# FPGA_34.net
KiCad netlist of a schematic drawn in Altium Designer
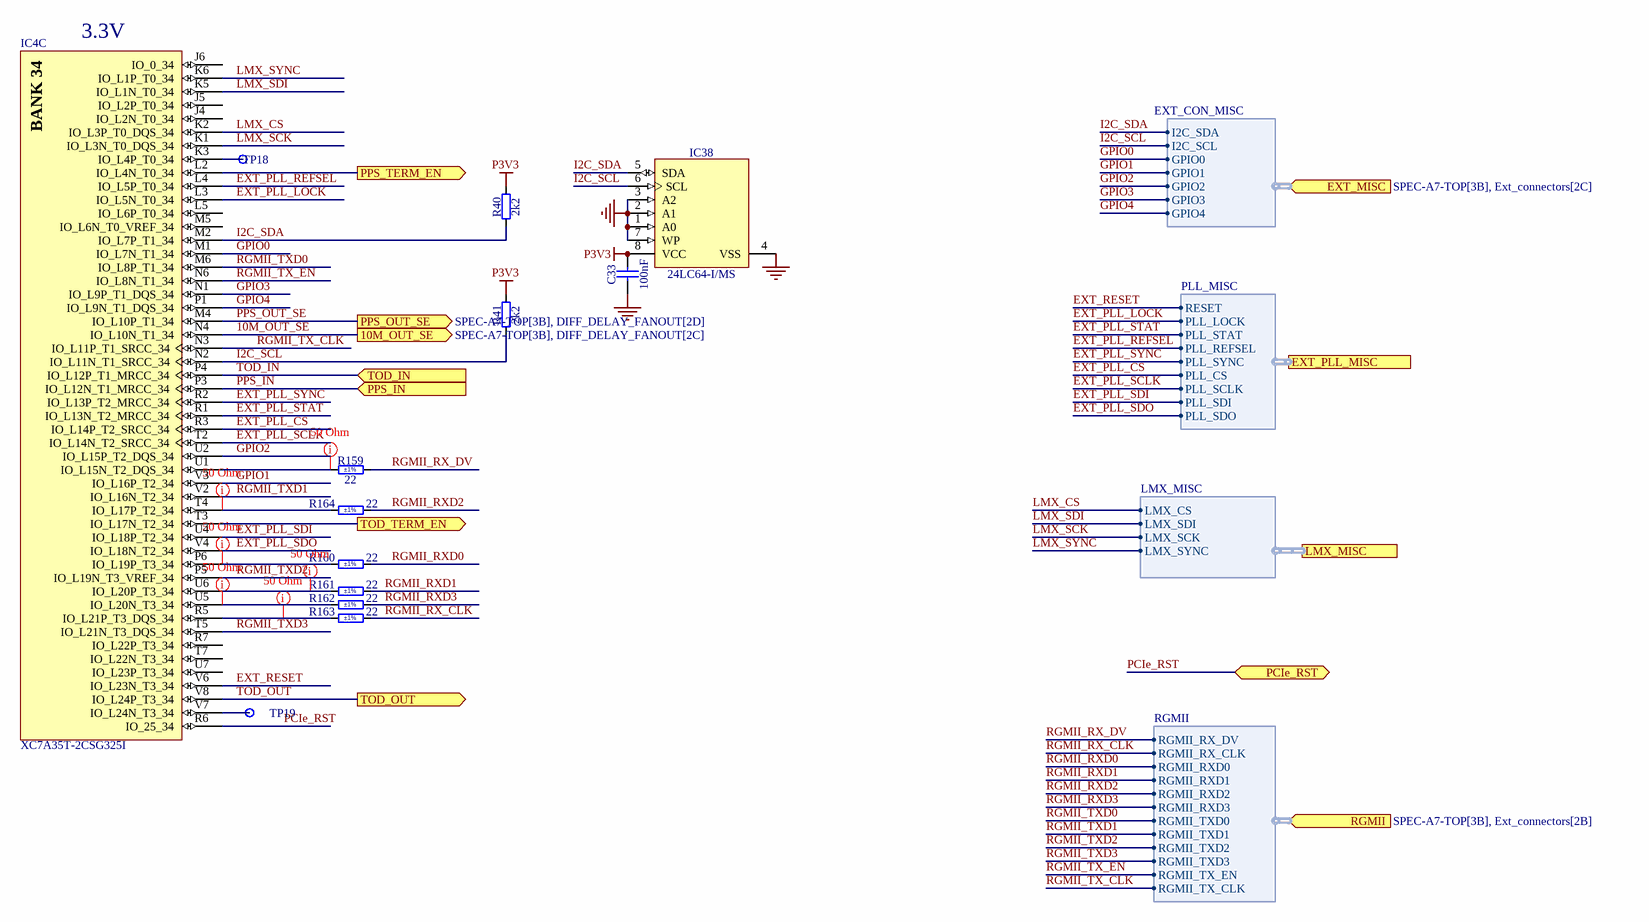
[diagram p0: FPGA_34.SchDoc]

(export (version "E")
  (design (tool "Eeschema 10.0.6"))
  (components
    (comp (ref "C33")
      (value "100nF")
      (footprint "CAPC0603X33N")
      (description "Non-polarised capacitor")
      (fields
        (field (name "PART NUMBER") "CC0201_100NF_6.3V_10%_X5R")
        (field (name "VOLTAGE") "6.3V")
        (field (name "AUTHOR") "CERN DEM JLC")
      )
      (libsource (lib "Capacitors") (part "Capacitor - non polarized"))
    )
    (comp (ref "IC4")
      (value "XC7A35T-2CSG325I")
      (footprint "CSG325")
      (description "Artix-7 FPGA, 150 User I/Os, 4 GTP, 324-Ball BGA, Speed Grade 2, Industrial Grade, Pb-Free")
      (fields (field (name "MANUFACTURER") "Xilinx"))
      (libsource (lib "Altium Content Vault") (part "XLNX-XC7A35T-CSG325"))
    )
    (comp (ref "IC38")
      (value "24LC64-I/MS")
      (footprint "SOP65P490X110-8N")
      (description "64K I2C Serial EEPROM")
      (fields (field (name "MANUFACTURER") "MICROCHIP TECHNOLOGY") (field (name "AUTHOR") "CERN DEM JLC"))
      (libsource (lib "ICs And Semiconductors") (part "24LC64-I/MS"))
    )
    (comp (ref "R40")
      (value "2k2")
      (footprint "RESC1005X40N")
      (description "Resistor - 1%")
      (fields
        (field (name "PART NUMBER") "R0402_2K2_1%_0.0625W_100PPM")
        (field (name "POWER") "0.0625W")
        (field (name "AUTHOR") "CERN DEM JLC")
      )
      (libsource (lib "Resistors") (part "Resistor - 1%"))
    )
    (comp (ref "R41")
      (value "2k2")
      (footprint "RESC1005X40N")
      (description "Resistor - 1%")
      (fields
        (field (name "PART NUMBER") "R0402_2K2_1%_0.0625W_100PPM")
        (field (name "POWER") "0.0625W")
        (field (name "AUTHOR") "CERN DEM JLC")
      )
      (libsource (lib "Resistors") (part "Resistor - 1%"))
    )
    (comp (ref "R159")
      (value "22")
      (footprint "RESC1005X40N")
      (description "Resistor - 1%")
      (fields
        (field (name "TOLERANCE") "±1%")
        (field (name "PART NUMBER") "R0402_22R_1%_0.0625W_100PPM")
        (field (name "POWER") "0.0625W")
        (field (name "AUTHOR") "CERN DEM JLC")
      )
      (libsource (lib "Resistors") (part "Resistor - 1%"))
    )
    (comp (ref "R160")
      (value "22")
      (footprint "RESC1005X40N")
      (description "Resistor - 1%")
      (fields
        (field (name "TOLERANCE") "±1%")
        (field (name "PART NUMBER") "R0402_22R_1%_0.0625W_100PPM")
        (field (name "POWER") "0.0625W")
        (field (name "AUTHOR") "CERN DEM JLC")
      )
      (libsource (lib "Resistors") (part "Resistor - 1%"))
    )
    (comp (ref "R161")
      (value "22")
      (footprint "RESC1005X40N")
      (description "Resistor - 1%")
      (fields
        (field (name "TOLERANCE") "±1%")
        (field (name "PART NUMBER") "R0402_22R_1%_0.0625W_100PPM")
        (field (name "POWER") "0.0625W")
        (field (name "AUTHOR") "CERN DEM JLC")
      )
      (libsource (lib "Resistors") (part "Resistor - 1%"))
    )
    (comp (ref "R162")
      (value "22")
      (footprint "RESC1005X40N")
      (description "Resistor - 1%")
      (fields
        (field (name "TOLERANCE") "±1%")
        (field (name "PART NUMBER") "R0402_22R_1%_0.0625W_100PPM")
        (field (name "POWER") "0.0625W")
        (field (name "AUTHOR") "CERN DEM JLC")
      )
      (libsource (lib "Resistors") (part "Resistor - 1%"))
    )
    (comp (ref "R163")
      (value "22")
      (footprint "RESC1005X40N")
      (description "Resistor - 1%")
      (fields
        (field (name "TOLERANCE") "±1%")
        (field (name "PART NUMBER") "R0402_22R_1%_0.0625W_100PPM")
        (field (name "POWER") "0.0625W")
        (field (name "AUTHOR") "CERN DEM JLC")
      )
      (libsource (lib "Resistors") (part "Resistor - 1%"))
    )
    (comp (ref "R164")
      (value "22")
      (footprint "RESC1005X40N")
      (description "Resistor - 1%")
      (fields
        (field (name "TOLERANCE") "±1%")
        (field (name "PART NUMBER") "R0402_22R_1%_0.0625W_100PPM")
        (field (name "POWER") "0.0625W")
        (field (name "AUTHOR") "CERN DEM JLC")
      )
      (libsource (lib "Resistors") (part "Resistor - 1%"))
    )
    (comp (ref "TP18")
      (value "Test Point")
      (footprint "TPS060")
      (fields (field (name "PART NUMBER") "SMD_PAD_0.6X0.6MM") (field (name "AUTHOR") "CERN DEM HF"))
      (libsource (lib "Eletro-mechanical") (part "Test Point"))
    )
    (comp (ref "TP19")
      (value "Test Point")
      (footprint "TPS060")
      (fields (field (name "PART NUMBER") "SMD_PAD_0.6X0.6MM") (field (name "AUTHOR") "CERN DEM HF"))
      (libsource (lib "Eletro-mechanical") (part "Test Point"))
    )
  )
  (nets
    (net (code "5") (name "/10M_OUT_SE") (class "Default")
      (node (ref "IC4") (pin "N4") (pinfunction "IO_L10N_T1_34_N4") (pintype "bidirectional"))
    )
    (net (code "6") (name "/EXT_PLL_CS") (class "Default")
      (node (ref "IC4") (pin "R3") (pinfunction "IO_L14P_T2_SRCC_34_R3") (pintype "bidirectional"))
    )
    (net (code "7") (name "/EXT_PLL_LOCK") (class "Default")
      (node (ref "IC4") (pin "L3") (pinfunction "IO_L5N_T0_34_L3") (pintype "bidirectional"))
    )
    (net (code "8") (name "/EXT_PLL_REFSEL") (class "Default")
      (node (ref "IC4") (pin "L4") (pinfunction "IO_L5P_T0_34_L4") (pintype "bidirectional"))
    )
    (net (code "9") (name "/EXT_PLL_SCLK") (class "Default")
      (node (ref "IC4") (pin "T2") (pinfunction "IO_L14N_T2_SRCC_34_T2") (pintype "bidirectional"))
    )
    (net (code "10") (name "/EXT_PLL_SDI") (class "Default")
      (node (ref "IC4") (pin "U4") (pinfunction "IO_L18P_T2_34_U4") (pintype "bidirectional"))
    )
    (net (code "11") (name "/EXT_PLL_SDO") (class "Default")
      (node (ref "IC4") (pin "V4") (pinfunction "IO_L18N_T2_34_V4") (pintype "bidirectional"))
    )
    (net (code "12") (name "/EXT_PLL_STAT") (class "Default")
      (node (ref "IC4") (pin "R1") (pinfunction "IO_L13N_T2_MRCC_34_R1") (pintype "bidirectional"))
    )
    (net (code "13") (name "/EXT_PLL_SYNC") (class "Default")
      (node (ref "IC4") (pin "R2") (pinfunction "IO_L13P_T2_MRCC_34_R2") (pintype "bidirectional"))
    )
    (net (code "14") (name "/EXT_RESET") (class "Default")
      (node (ref "IC4") (pin "V6") (pinfunction "IO_L23N_T3_34_V6") (pintype "bidirectional"))
    )
    (net (code "15") (name "/GPIO0") (class "Default")
      (node (ref "IC4") (pin "M1") (pinfunction "IO_L7N_T1_34_M1") (pintype "bidirectional"))
    )
    (net (code "16") (name "/GPIO1") (class "Default")
      (node (ref "IC4") (pin "V3") (pinfunction "IO_L16P_T2_34_V3") (pintype "bidirectional"))
    )
    (net (code "17") (name "/GPIO2") (class "Default")
      (node (ref "IC4") (pin "U2") (pinfunction "IO_L15P_T2_DQS_34_U2") (pintype "bidirectional"))
    )
    (net (code "18") (name "/GPIO3") (class "Default")
      (node (ref "IC4") (pin "N1") (pinfunction "IO_L9P_T1_DQS_34_N1") (pintype "bidirectional"))
    )
    (net (code "19") (name "/GPIO4") (class "Default")
      (node (ref "IC4") (pin "P1") (pinfunction "IO_L9N_T1_DQS_34_P1") (pintype "bidirectional"))
    )
    (net (code "20") (name "/I2C_SCL") (class "Default")
      (node (ref "IC38") (pin "6") (pinfunction "SCL_6") (pintype "input"))
      (node (ref "IC4") (pin "N2") (pinfunction "IO_L11N_T1_SRCC_34_N2") (pintype "bidirectional"))
      (node (ref "R41") (pin "1") (pinfunction "1_1") (pintype "passive"))
    )
    (net (code "21") (name "/I2C_SDA") (class "Default")
      (node (ref "IC38") (pin "5") (pinfunction "SDA_5") (pintype "bidirectional"))
      (node (ref "IC4") (pin "M2") (pinfunction "IO_L7P_T1_34_M2") (pintype "bidirectional"))
      (node (ref "R40") (pin "1") (pinfunction "1_1") (pintype "passive"))
    )
    (net (code "22") (name "/LMX_CS") (class "Default")
      (node (ref "IC4") (pin "K2") (pinfunction "IO_L3P_T0_DQS_34_K2") (pintype "bidirectional"))
    )
    (net (code "23") (name "/LMX_SCK") (class "Default")
      (node (ref "IC4") (pin "K1") (pinfunction "IO_L3N_T0_DQS_34_K1") (pintype "bidirectional"))
    )
    (net (code "24") (name "/LMX_SDI") (class "Default")
      (node (ref "IC4") (pin "K5") (pinfunction "IO_L1N_T0_34_K5") (pintype "bidirectional"))
    )
    (net (code "25") (name "/LMX_SYNC") (class "Default")
      (node (ref "IC4") (pin "K6") (pinfunction "IO_L1P_T0_34_K6") (pintype "bidirectional"))
    )
    (net (code "26") (name "/PCIe_RST") (class "Default")
      (node (ref "IC4") (pin "R6") (pinfunction "IO_25_34_R6") (pintype "bidirectional"))
    )
    (net (code "27") (name "/PPS_IN") (class "Default")
      (node (ref "IC4") (pin "P3") (pinfunction "IO_L12N_T1_MRCC_34_P3") (pintype "bidirectional"))
    )
    (net (code "28") (name "/PPS_OUT_SE") (class "Default")
      (node (ref "IC4") (pin "M4") (pinfunction "IO_L10P_T1_34_M4") (pintype "bidirectional"))
    )
    (net (code "29") (name "/PPS_TERM_EN") (class "Default")
      (node (ref "IC4") (pin "L2") (pinfunction "IO_L4N_T0_34_L2") (pintype "bidirectional"))
    )
    (net (code "30") (name "/RGMII_RXD0") (class "Default")
      (node (ref "R160") (pin "2") (pinfunction "2_2") (pintype "passive"))
    )
    (net (code "31") (name "/RGMII_RXD1") (class "Default")
      (node (ref "R161") (pin "2") (pinfunction "2_2") (pintype "passive"))
    )
    (net (code "32") (name "/RGMII_RXD2") (class "Default")
      (node (ref "R164") (pin "2") (pinfunction "2_2") (pintype "passive"))
    )
    (net (code "33") (name "/RGMII_RXD3") (class "Default")
      (node (ref "R162") (pin "2") (pinfunction "2_2") (pintype "passive"))
    )
    (net (code "34") (name "/RGMII_RX_CLK") (class "Default")
      (node (ref "R163") (pin "2") (pinfunction "2_2") (pintype "passive"))
    )
    (net (code "35") (name "/RGMII_RX_DV") (class "Default")
      (node (ref "R159") (pin "2") (pinfunction "2_2") (pintype "passive"))
    )
    (net (code "36") (name "/RGMII_TXD0") (class "Default")
      (node (ref "IC4") (pin "M6") (pinfunction "IO_L8P_T1_34_M6") (pintype "bidirectional"))
    )
    (net (code "37") (name "/RGMII_TXD1") (class "Default")
      (node (ref "IC4") (pin "V2") (pinfunction "IO_L16N_T2_34_V2") (pintype "bidirectional"))
    )
    (net (code "38") (name "/RGMII_TXD2") (class "Default")
      (node (ref "IC4") (pin "P5") (pinfunction "IO_L19N_T3_VREF_34_P5") (pintype "bidirectional"))
    )
    (net (code "39") (name "/RGMII_TXD3") (class "Default")
      (node (ref "IC4") (pin "T5") (pinfunction "IO_L21N_T3_DQS_34_T5") (pintype "bidirectional"))
    )
    (net (code "40") (name "/RGMII_TX_CLK") (class "Default")
      (node (ref "IC4") (pin "N3") (pinfunction "IO_L11P_T1_SRCC_34_N3") (pintype "bidirectional"))
    )
    (net (code "41") (name "/RGMII_TX_EN") (class "Default")
      (node (ref "IC4") (pin "N6") (pinfunction "IO_L8N_T1_34_N6") (pintype "bidirectional"))
    )
    (net (code "42") (name "/TOD_IN") (class "Default")
      (node (ref "IC4") (pin "P4") (pinfunction "IO_L12P_T1_MRCC_34_P4") (pintype "bidirectional"))
    )
    (net (code "43") (name "/TOD_OUT") (class "Default")
      (node (ref "IC4") (pin "V8") (pinfunction "IO_L24P_T3_34_V8") (pintype "bidirectional"))
    )
    (net (code "44") (name "/TOD_TERM_EN") (class "Default")
      (node (ref "IC4") (pin "T3") (pinfunction "IO_L17N_T2_34_T3") (pintype "bidirectional"))
    )
    (net (code "49") (name "GND") (class "Default")
      (node (ref "C33") (pin "1") (pinfunction "1_1") (pintype "passive"))
      (node (ref "IC38") (pin "1") (pinfunction "A0_1") (pintype "input"))
      (node (ref "IC38") (pin "2") (pinfunction "A1_2") (pintype "input"))
      (node (ref "IC38") (pin "3") (pinfunction "A2_3") (pintype "input"))
      (node (ref "IC38") (pin "4") (pinfunction "VSS_4") (pintype "power_in"))
      (node (ref "IC38") (pin "7") (pinfunction "WP_7") (pintype "input"))
    )
    (net (code "50") (name "Net-(IC4C-IO_L4P_T0_34)") (class "Default")
      (node (ref "IC4") (pin "K3") (pinfunction "IO_L4P_T0_34_K3") (pintype "bidirectional"))
      (node (ref "TP18") (pin "1") (pinfunction "1_1") (pintype "bidirectional"))
    )
    (net (code "51") (name "Net-(IC4C-IO_L15N_T2_DQS_34)") (class "Default")
      (node (ref "IC4") (pin "U1") (pinfunction "IO_L15N_T2_DQS_34_U1") (pintype "bidirectional"))
      (node (ref "R159") (pin "1") (pinfunction "1_1") (pintype "passive"))
    )
    (net (code "52") (name "Net-(IC4C-IO_L17P_T2_34)") (class "Default")
      (node (ref "IC4") (pin "T4") (pinfunction "IO_L17P_T2_34_T4") (pintype "bidirectional"))
      (node (ref "R164") (pin "1") (pinfunction "1_1") (pintype "passive"))
    )
    (net (code "53") (name "Net-(IC4C-IO_L19P_T3_34)") (class "Default")
      (node (ref "IC4") (pin "P6") (pinfunction "IO_L19P_T3_34_P6") (pintype "bidirectional"))
      (node (ref "R160") (pin "1") (pinfunction "1_1") (pintype "passive"))
    )
    (net (code "54") (name "Net-(IC4C-IO_L20N_T3_34)") (class "Default")
      (node (ref "IC4") (pin "U5") (pinfunction "IO_L20N_T3_34_U5") (pintype "bidirectional"))
      (node (ref "R162") (pin "1") (pinfunction "1_1") (pintype "passive"))
    )
    (net (code "55") (name "Net-(IC4C-IO_L20P_T3_34)") (class "Default")
      (node (ref "IC4") (pin "U6") (pinfunction "IO_L20P_T3_34_U6") (pintype "bidirectional"))
      (node (ref "R161") (pin "1") (pinfunction "1_1") (pintype "passive"))
    )
    (net (code "56") (name "Net-(IC4C-IO_L21P_T3_DQS_34)") (class "Default")
      (node (ref "IC4") (pin "R5") (pinfunction "IO_L21P_T3_DQS_34_R5") (pintype "bidirectional"))
      (node (ref "R163") (pin "1") (pinfunction "1_1") (pintype "passive"))
    )
    (net (code "57") (name "Net-(IC4C-IO_L24N_T3_34)") (class "Default")
      (node (ref "IC4") (pin "V7") (pinfunction "IO_L24N_T3_34_V7") (pintype "bidirectional"))
      (node (ref "TP19") (pin "1") (pinfunction "1_1") (pintype "bidirectional"))
    )
    (net (code "58") (name "P3V3") (class "Default")
      (node (ref "C33") (pin "2") (pinfunction "2_2") (pintype "passive"))
      (node (ref "IC38") (pin "8") (pinfunction "VCC_8") (pintype "power_in"))
      (node (ref "R40") (pin "2") (pinfunction "2_2") (pintype "passive"))
      (node (ref "R41") (pin "2") (pinfunction "2_2") (pintype "passive"))
    )
    (net (code "59") (name "unconnected-(IC4C-IO_0_34-PadJ6)") (class "Default")
      (node (ref "IC4") (pin "J6") (pinfunction "IO_0_34_J6") (pintype "bidirectional"))
    )
    (net (code "60") (name "unconnected-(IC4C-IO_L2N_T0_34-PadJ4)") (class "Default")
      (node (ref "IC4") (pin "J4") (pinfunction "IO_L2N_T0_34_J4") (pintype "bidirectional"))
    )
    (net (code "61") (name "unconnected-(IC4C-IO_L2P_T0_34-PadJ5)") (class "Default")
      (node (ref "IC4") (pin "J5") (pinfunction "IO_L2P_T0_34_J5") (pintype "bidirectional"))
    )
    (net (code "62") (name "unconnected-(IC4C-IO_L6N_T0_VREF_34-PadM5)") (class "Default")
      (node (ref "IC4") (pin "M5") (pinfunction "IO_L6N_T0_VREF_34_M5") (pintype "bidirectional"))
    )
    (net (code "63") (name "unconnected-(IC4C-IO_L6P_T0_34-PadL5)") (class "Default")
      (node (ref "IC4") (pin "L5") (pinfunction "IO_L6P_T0_34_L5") (pintype "bidirectional"))
    )
    (net (code "64") (name "unconnected-(IC4C-IO_L22N_T3_34-PadT7)") (class "Default")
      (node (ref "IC4") (pin "T7") (pinfunction "IO_L22N_T3_34_T7") (pintype "bidirectional"))
    )
    (net (code "65") (name "unconnected-(IC4C-IO_L22P_T3_34-PadR7)") (class "Default")
      (node (ref "IC4") (pin "R7") (pinfunction "IO_L22P_T3_34_R7") (pintype "bidirectional"))
    )
    (net (code "66") (name "unconnected-(IC4C-IO_L23P_T3_34-PadU7)") (class "Default")
      (node (ref "IC4") (pin "U7") (pinfunction "IO_L23P_T3_34_U7") (pintype "bidirectional"))
    )
  )
)
